# Zuino_XS_PsyFi32.net
KiCad netlist of a schematic drawn in EAGLE
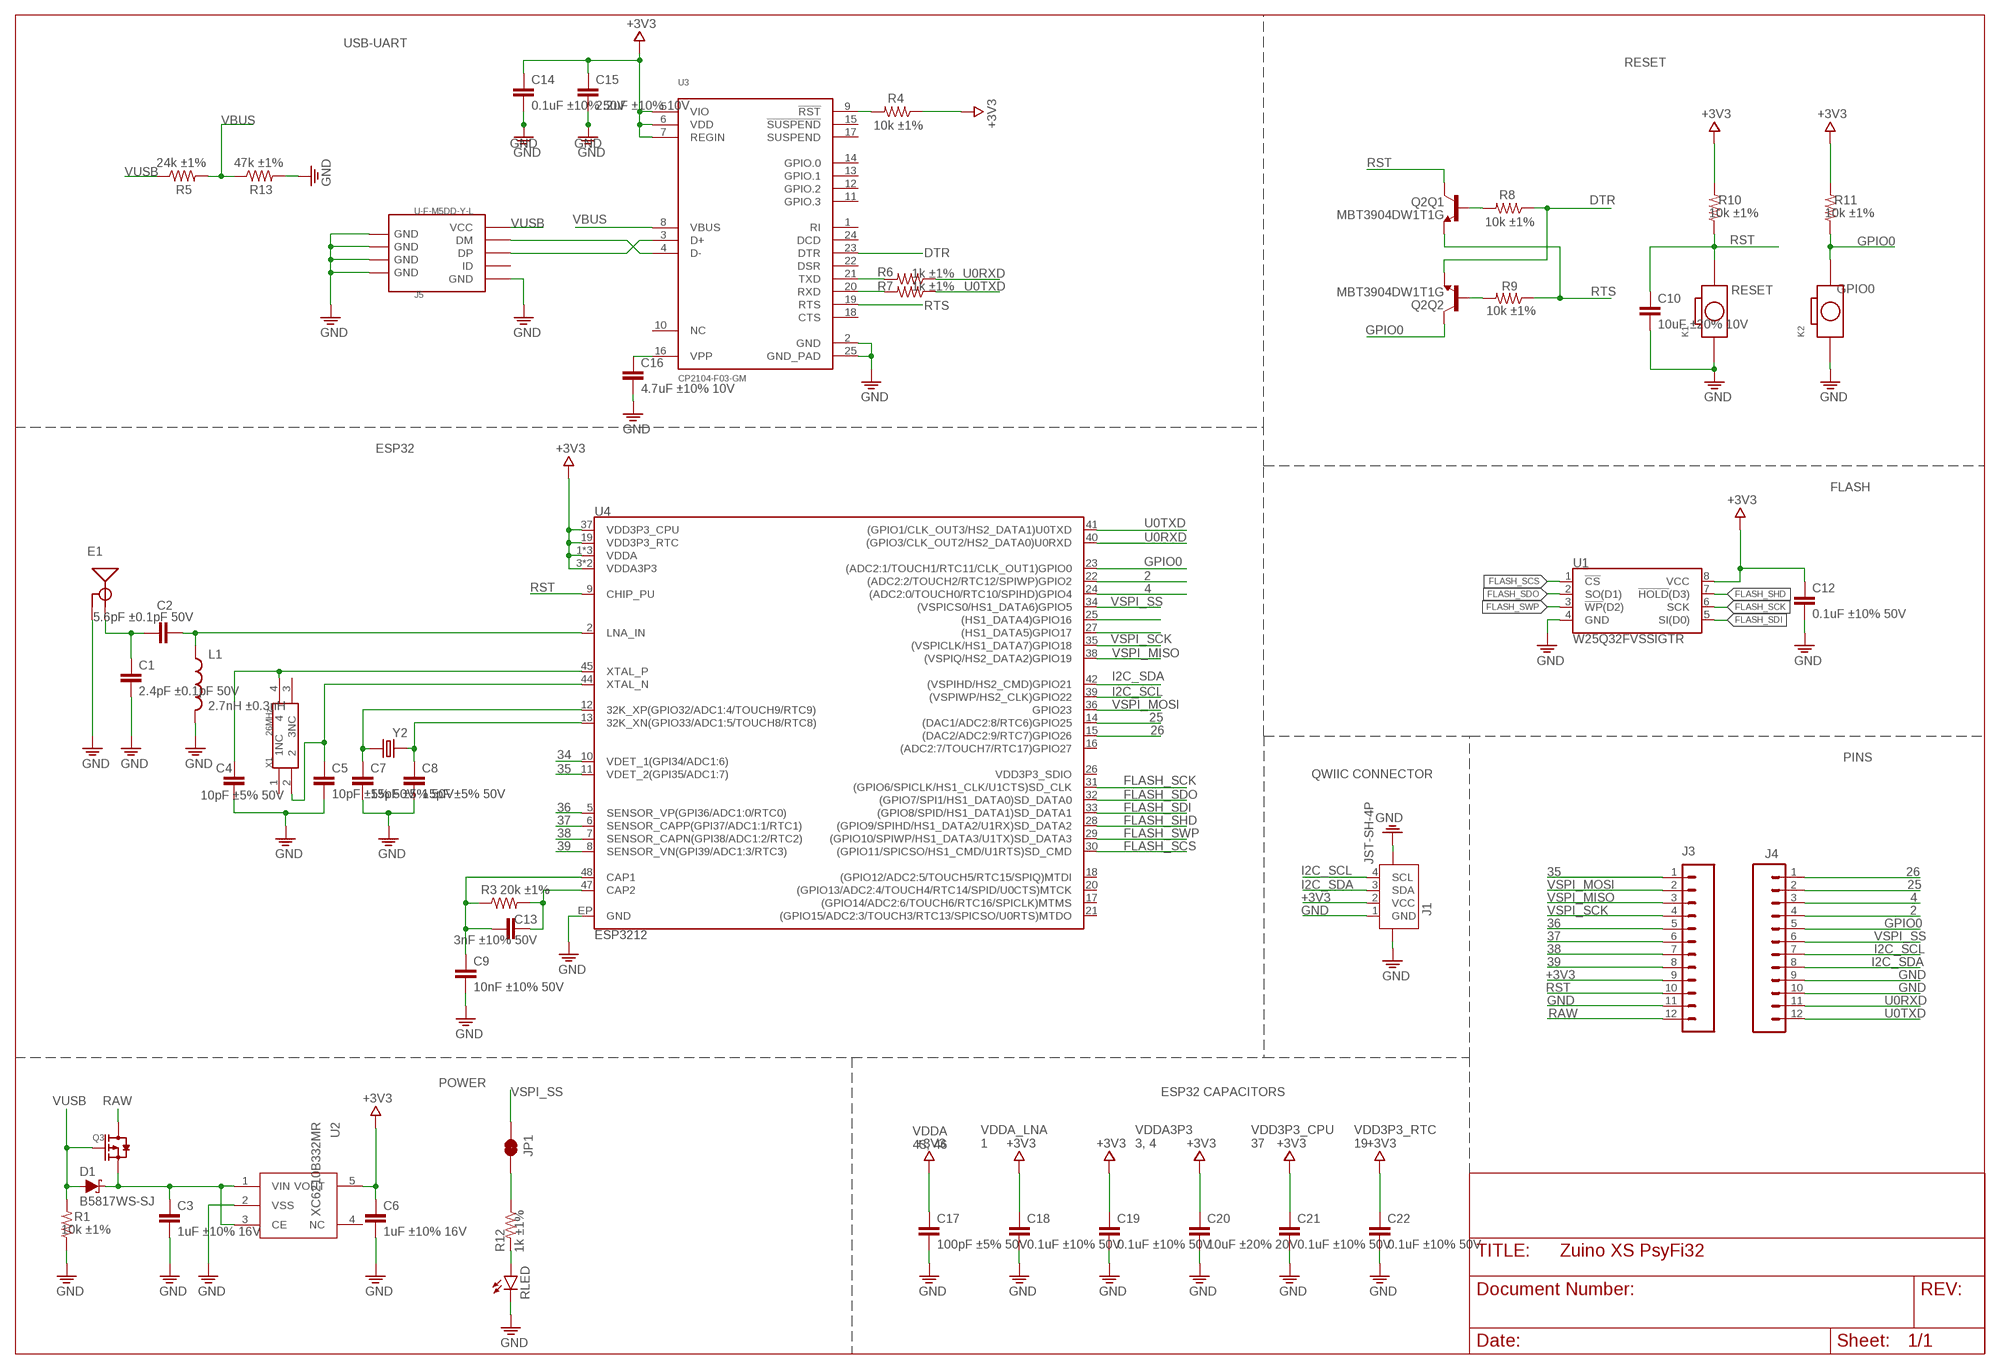
[diagram p0: schematic, sheet 1]

(export (version "E")
  (design (tool "Eeschema 10.0.6"))
  (components
    (comp (ref "C1")
      (value "2.4pF ±0.1pF 50V")
      (footprint "eagle-import:YAGEO_C_0402")
      (libsource (lib "eagle-import") (part "0.1UF"))
    )
    (comp (ref "C2")
      (value "5.6pF ±0.1pF 50V")
      (footprint "eagle-import:YAGEO_C_0402")
      (libsource (lib "eagle-import") (part "0.1UF"))
    )
    (comp (ref "C3")
      (value "1uF ±10% 16V")
      (footprint "eagle-import:YAGEO_C_0402")
      (libsource (lib "eagle-import") (part "0.1UF"))
    )
    (comp (ref "C4")
      (value "10pF ±5% 50V")
      (footprint "eagle-import:YAGEO_C_0402")
      (libsource (lib "eagle-import") (part "0.1UF"))
    )
    (comp (ref "C5")
      (value "10pF ±5% 50V")
      (footprint "eagle-import:YAGEO_C_0402")
      (libsource (lib "eagle-import") (part "0.1UF"))
    )
    (comp (ref "C6")
      (value "1uF ±10% 16V")
      (footprint "eagle-import:YAGEO_C_0402")
      (libsource (lib "eagle-import") (part "0.1UF"))
    )
    (comp (ref "C7")
      (value "15pF ±5% 50V")
      (footprint "eagle-import:YAGEO_C_0402")
      (libsource (lib "eagle-import") (part "0.1UF"))
    )
    (comp (ref "C8")
      (value "15pF ±5% 50V")
      (footprint "eagle-import:YAGEO_C_0402")
      (libsource (lib "eagle-import") (part "0.1UF"))
    )
    (comp (ref "C9")
      (value "10nF ±10% 50V")
      (footprint "eagle-import:YAGEO_C_0402")
      (libsource (lib "eagle-import") (part "0.1UF"))
    )
    (comp (ref "C10")
      (value "10uF ±20% 10V")
      (footprint "eagle-import:YAGEO_C_0402")
      (libsource (lib "eagle-import") (part "0.1UF"))
    )
    (comp (ref "C12")
      (value "0.1uF ±10% 50V")
      (footprint "eagle-import:YAGEO_C_0402")
      (libsource (lib "eagle-import") (part "0.1UF"))
    )
    (comp (ref "C13")
      (value "3nF ±10% 50V")
      (footprint "eagle-import:YAGEO_C_0402")
      (libsource (lib "eagle-import") (part "0.1UF"))
    )
    (comp (ref "C14")
      (value "0.1uF ±10% 50V")
      (footprint "eagle-import:YAGEO_C_0402")
      (libsource (lib "eagle-import") (part "0.1UF"))
    )
    (comp (ref "C15")
      (value "2.2uF ±10% 10V")
      (footprint "eagle-import:YAGEO_C_0402")
      (libsource (lib "eagle-import") (part "0.1UF"))
    )
    (comp (ref "C16")
      (value "4.7uF ±10% 10V")
      (footprint "eagle-import:YAGEO_C_0402")
      (libsource (lib "eagle-import") (part "0.1UF"))
    )
    (comp (ref "C17")
      (value "100pF ±5% 50V")
      (footprint "eagle-import:YAGEO_C_0402")
      (libsource (lib "eagle-import") (part "0.1UF"))
    )
    (comp (ref "C18")
      (value "0.1uF ±10% 50V")
      (footprint "eagle-import:YAGEO_C_0402")
      (libsource (lib "eagle-import") (part "0.1UF"))
    )
    (comp (ref "C19")
      (value "0.1uF ±10% 50V")
      (footprint "eagle-import:YAGEO_C_0402")
      (libsource (lib "eagle-import") (part "0.1UF"))
    )
    (comp (ref "C20")
      (value "10uF ±20% 20V")
      (footprint "eagle-import:YAGEO_C_0402")
      (libsource (lib "eagle-import") (part "0.1UF"))
    )
    (comp (ref "C21")
      (value "0.1uF ±10% 50V")
      (footprint "eagle-import:YAGEO_C_0402")
      (libsource (lib "eagle-import") (part "0.1UF"))
    )
    (comp (ref "C22")
      (value "0.1uF ±10% 50V")
      (footprint "eagle-import:YAGEO_C_0402")
      (libsource (lib "eagle-import") (part "0.1UF"))
    )
    (comp (ref "D1")
      (value "B5817WS-SJ")
      (footprint "eagle-import:SOD-323")
      (libsource (lib "eagle-import") (part "DIODE-SCHOTTKY-BAT20J"))
    )
    (comp (ref "D2")
      (value "RLED")
      (footprint "eagle-import:LED_HSMH-C190")
      (libsource (lib "eagle-import") (part "LED"))
    )
    (comp (ref "E1")
      (value "ANTENNA-GROUNDED")
      (footprint "eagle-import:ANTENNA_ESP32")
      (libsource (lib "eagle-import") (part "ANTENNA-GROUNDED"))
    )
    (comp (ref "J1")
      (value "JST-SH-4P")
      (footprint "eagle-import:JST-SH-4P-90")
      (libsource (lib "eagle-import") (part "JST-SH-4P"))
    )
    (comp (ref "J3")
      (value "CONN_12")
      (footprint "eagle-import:1X12")
      (libsource (lib "eagle-import") (part "CONN_12"))
    )
    (comp (ref "J4")
      (value "CONN_12")
      (footprint "eagle-import:1X12")
      (libsource (lib "eagle-import") (part "CONN_12"))
    )
    (comp (ref "J5")
      (value "U-F-M5DD-Y-L")
      (footprint "eagle-import:MICRO-SMD")
      (libsource (lib "eagle-import") (part "USB-MICROE"))
    )
    (comp (ref "JP1")
      (value "JUMPER-SMT_2_NC_TRACE_SILK")
      (footprint "eagle-import:SMT-JUMPER_2_NC_TRACE_SILK")
      (libsource (lib "eagle-import") (part "JUMPER-SMT_2_NC_TRACE_SILK"))
    )
    (comp (ref "K1")
      (value "BOTTON-2PSKRKAEE020")
      (footprint "eagle-import:SKRKAEE020")
      (libsource (lib "eagle-import") (part "BOTTON-2PSKRKAEE020"))
    )
    (comp (ref "K2")
      (value "BOTTON-2PSKRKAEE020")
      (footprint "eagle-import:SKRKAEE020")
      (libsource (lib "eagle-import") (part "BOTTON-2PSKRKAEE020"))
    )
    (comp (ref "L1")
      (value "2.7nH ±0.3nH")
      (footprint "eagle-import:INDUCTOR_HK10052N7S-T")
      (libsource (lib "eagle-import") (part "INDUCTOR"))
    )
    (comp (ref "Q2")
      (value "MBT3904DW1T1G")
      (footprint "eagle-import:SC70-6")
      (fields
        (field (name "DIGIKEY") "https://www.digikey.com/product-detail/en/on-semiconductor/MBT3904DW1T1G/MBT3904DW1T1GOSCT-ND/918012")
      )
      (libsource (lib "eagle-import") (part "MBT3904DW1T1"))
    )
    (comp (ref "Q3")
      (value "MOSFET-P-323")
      (footprint "eagle-import:SOT-323")
      (libsource (lib "eagle-import") (part "MOSFET-P-323"))
    )
    (comp (ref "R1")
      (value "10k ±1%")
      (footprint "eagle-import:YAGEO_R_0402")
      (libsource (lib "eagle-import") (part "RESISTOR"))
    )
    (comp (ref "R3")
      (value "20k ±1%")
      (footprint "eagle-import:YAGEO_R_0402")
      (libsource (lib "eagle-import") (part "RESISTOR"))
    )
    (comp (ref "R4")
      (value "10k ±1%")
      (footprint "eagle-import:YAGEO_R_0402")
      (libsource (lib "eagle-import") (part "RESISTOR"))
    )
    (comp (ref "R5")
      (value "24k ±1%")
      (footprint "eagle-import:YAGEO_R_0402")
      (libsource (lib "eagle-import") (part "RESISTOR"))
    )
    (comp (ref "R6")
      (value "1k ±1%")
      (footprint "eagle-import:YAGEO_R_0402")
      (libsource (lib "eagle-import") (part "RESISTOR"))
    )
    (comp (ref "R7")
      (value "1k ±1%")
      (footprint "eagle-import:YAGEO_R_0402")
      (libsource (lib "eagle-import") (part "RESISTOR"))
    )
    (comp (ref "R8")
      (value "10k ±1%")
      (footprint "eagle-import:YAGEO_R_0402")
      (libsource (lib "eagle-import") (part "RESISTOR"))
    )
    (comp (ref "R9")
      (value "10k ±1%")
      (footprint "eagle-import:YAGEO_R_0402")
      (libsource (lib "eagle-import") (part "RESISTOR"))
    )
    (comp (ref "R10")
      (value "10k ±1%")
      (footprint "eagle-import:YAGEO_R_0402")
      (libsource (lib "eagle-import") (part "RESISTOR"))
    )
    (comp (ref "R11")
      (value "10k ±1%")
      (footprint "eagle-import:YAGEO_R_0402")
      (libsource (lib "eagle-import") (part "RESISTOR"))
    )
    (comp (ref "R12")
      (value "1k ±1%")
      (footprint "eagle-import:YAGEO_R_0402")
      (libsource (lib "eagle-import") (part "RESISTOR"))
    )
    (comp (ref "R13")
      (value "47k ±1%")
      (footprint "eagle-import:YAGEO_R_0402")
      (libsource (lib "eagle-import") (part "RESISTOR"))
    )
    (comp (ref "U1")
      (value "W25Q32FVSSIGTR")
      (footprint "eagle-import:SOIC-8")
      (libsource (lib "eagle-import") (part "W25Q32FVSS"))
    )
    (comp (ref "U2")
      (value "XC6210B332MR")
      (footprint "eagle-import:SOT23-5")
      (libsource (lib "eagle-import") (part "XC6210"))
    )
    (comp (ref "U3")
      (value "CP2104-F03-GM")
      (footprint "eagle-import:QFN24-CP2104")
      (libsource (lib "eagle-import") (part "CP2104-F03-GM"))
    )
    (comp (ref "U4")
      (value "ESP3212")
      (footprint "eagle-import:QFN48-0.4MM")
      (libsource (lib "eagle-import") (part "ESP3212"))
    )
    (comp (ref "X1")
      (value "26MHz")
      (footprint "eagle-import:4P-SMD-2X1.6MM")
      (libsource (lib "eagle-import") (part "CRYSTAL-XTAL-4P"))
    )
    (comp (ref "Y2")
      (value "32.768kHz")
      (footprint "eagle-import:CRYSTAL_2012")
      (libsource (lib "eagle-import") (part "CRYSTAL-Y2012"))
    )
  )
  (nets
    (net (code "1") (name "+3V3") (class "Default")
      (node (ref "C12") (pin "1") (pinfunction "1_1") (pintype "passive"))
      (node (ref "C14") (pin "1") (pinfunction "1_1") (pintype "passive"))
      (node (ref "C15") (pin "1") (pinfunction "1_1") (pintype "passive"))
      (node (ref "C17") (pin "1") (pinfunction "1_1") (pintype "passive"))
      (node (ref "C18") (pin "1") (pinfunction "1_1") (pintype "passive"))
      (node (ref "C19") (pin "1") (pinfunction "1_1") (pintype "passive"))
      (node (ref "C20") (pin "1") (pinfunction "1_1") (pintype "passive"))
      (node (ref "C21") (pin "1") (pinfunction "1_1") (pintype "passive"))
      (node (ref "C22") (pin "1") (pinfunction "1_1") (pintype "passive"))
      (node (ref "C6") (pin "1") (pinfunction "1_1") (pintype "passive"))
      (node (ref "J1") (pin "2") (pinfunction "VCC_2") (pintype "bidirectional"))
      (node (ref "J3") (pin "9") (pinfunction "9_9") (pintype "passive"))
      (node (ref "R10") (pin "2") (pinfunction "2_2") (pintype "passive"))
      (node (ref "R11") (pin "2") (pinfunction "2_2") (pintype "passive"))
      (node (ref "R4") (pin "1") (pinfunction "1_1") (pintype "passive"))
      (node (ref "U1") (pin "8") (pinfunction "VCC_8") (pintype "bidirectional"))
      (node (ref "U2") (pin "5") (pinfunction "VOUT_5") (pintype "bidirectional"))
      (node (ref "U3") (pin "5") (pinfunction "VIO_5") (pintype "bidirectional"))
      (node (ref "U3") (pin "6") (pinfunction "VDD_6") (pintype "bidirectional"))
      (node (ref "U3") (pin "7") (pinfunction "REGIN_7") (pintype "bidirectional"))
      (node (ref "U4") (pin "1") (pinfunction "VDDA_1") (pintype "bidirectional"))
      (node (ref "U4") (pin "19") (pinfunction "VDD3P3_RTC_19") (pintype "bidirectional"))
      (node (ref "U4") (pin "3") (pinfunction "VDDA3P3_3") (pintype "bidirectional"))
      (node (ref "U4") (pin "37") (pinfunction "VDD3P3_CPU_37") (pintype "bidirectional"))
      (node (ref "U4") (pin "4") (pinfunction "VDDA3P3_4") (pintype "bidirectional"))
      (node (ref "U4") (pin "43") (pinfunction "VDDA_43") (pintype "bidirectional"))
      (node (ref "U4") (pin "46") (pinfunction "VDDA_46") (pintype "bidirectional"))
    )
    (net (code "2") (name "/2") (class "Default")
      (node (ref "J4") (pin "4") (pinfunction "4_4") (pintype "passive"))
      (node (ref "U4") (pin "22") (pinfunction "(ADC2:2/TOUCH2/RTC12/SPIWP)GPIO2_22") (pintype "bidirectional"))
    )
    (net (code "3") (name "/4") (class "Default")
      (node (ref "J4") (pin "3") (pinfunction "3_3") (pintype "passive"))
      (node (ref "U4") (pin "24") (pinfunction "(ADC2:0/TOUCH0/RTC10/SPIHD)GPIO4_24") (pintype "bidirectional"))
    )
    (net (code "4") (name "/25") (class "Default")
      (node (ref "J4") (pin "2") (pinfunction "2_2") (pintype "passive"))
      (node (ref "U4") (pin "14") (pinfunction "(DAC1/ADC2:8/RTC6)GPIO25_14") (pintype "bidirectional"))
    )
    (net (code "5") (name "/26") (class "Default")
      (node (ref "J4") (pin "1") (pinfunction "1_1") (pintype "passive"))
      (node (ref "U4") (pin "15") (pinfunction "(DAC2/ADC2:9/RTC7)GPIO26_15") (pintype "bidirectional"))
    )
    (net (code "6") (name "/34") (class "Default")
      (node (ref "U4") (pin "10") (pinfunction "VDET_1(GPI34/ADC1:6)_10") (pintype "bidirectional"))
    )
    (net (code "7") (name "/35") (class "Default")
      (node (ref "J3") (pin "1") (pinfunction "1_1") (pintype "passive"))
      (node (ref "U4") (pin "11") (pinfunction "VDET_2(GPI35/ADC1:7)_11") (pintype "bidirectional"))
    )
    (net (code "8") (name "/36") (class "Default")
      (node (ref "J3") (pin "5") (pinfunction "5_5") (pintype "passive"))
      (node (ref "U4") (pin "5") (pinfunction "SENSOR_VP(GPI36/ADC1:0/RTC0)_5") (pintype "bidirectional"))
    )
    (net (code "9") (name "/37") (class "Default")
      (node (ref "J3") (pin "6") (pinfunction "6_6") (pintype "passive"))
      (node (ref "U4") (pin "6") (pinfunction "SENSOR_CAPP(GPI37/ADC1:1/RTC1)_6") (pintype "bidirectional"))
    )
    (net (code "10") (name "/38") (class "Default")
      (node (ref "J3") (pin "7") (pinfunction "7_7") (pintype "passive"))
      (node (ref "U4") (pin "7") (pinfunction "SENSOR_CAPN(GPI38/ADC1:2/RTC2)_7") (pintype "bidirectional"))
    )
    (net (code "11") (name "/39") (class "Default")
      (node (ref "J3") (pin "8") (pinfunction "8_8") (pintype "passive"))
      (node (ref "U4") (pin "8") (pinfunction "SENSOR_VN(GPI39/ADC1:3/RTC3)_8") (pintype "bidirectional"))
    )
    (net (code "12") (name "/DTR") (class "Default")
      (node (ref "Q2") (pin "1") (pinfunction "E_1") (pintype "passive"))
      (node (ref "R8") (pin "1") (pinfunction "1_1") (pintype "passive"))
      (node (ref "U3") (pin "23") (pinfunction "DTR_23") (pintype "bidirectional"))
    )
    (net (code "13") (name "/GPIO0") (class "Default")
      (node (ref "J4") (pin "5") (pinfunction "5_5") (pintype "passive"))
      (node (ref "K2") (pin "2") (pinfunction "2_2") (pintype "bidirectional"))
      (node (ref "Q2") (pin "6") (pinfunction "C_6") (pintype "passive"))
      (node (ref "R11") (pin "1") (pinfunction "1_1") (pintype "passive"))
      (node (ref "U4") (pin "23") (pinfunction "(ADC2:1/TOUCH1/RTC11/CLK_OUT1)GPIO0_23") (pintype "bidirectional"))
    )
    (net (code "14") (name "/I2C_SCL") (class "Default")
      (node (ref "J1") (pin "4") (pinfunction "SCL_4") (pintype "bidirectional"))
      (node (ref "J4") (pin "7") (pinfunction "7_7") (pintype "passive"))
      (node (ref "U4") (pin "39") (pinfunction "(VSPIWP/HS2_CLK)GPIO22_39") (pintype "bidirectional"))
    )
    (net (code "15") (name "/I2C_SDA") (class "Default")
      (node (ref "J1") (pin "3") (pinfunction "SDA_3") (pintype "bidirectional"))
      (node (ref "J4") (pin "8") (pinfunction "8_8") (pintype "passive"))
      (node (ref "U4") (pin "42") (pinfunction "(VSPIHD/HS2_CMD)GPIO21_42") (pintype "bidirectional"))
    )
    (net (code "16") (name "/RAW") (class "Default")
      (node (ref "J3") (pin "12") (pinfunction "12_12") (pintype "passive"))
      (node (ref "Q3") (pin "3") (pinfunction "D_3") (pintype "passive"))
    )
    (net (code "17") (name "/RST") (class "Default")
      (node (ref "C10") (pin "1") (pinfunction "1_1") (pintype "passive"))
      (node (ref "J3") (pin "10") (pinfunction "10_10") (pintype "passive"))
      (node (ref "K1") (pin "2") (pinfunction "2_2") (pintype "bidirectional"))
      (node (ref "Q2") (pin "3") (pinfunction "C_3") (pintype "passive"))
      (node (ref "R10") (pin "1") (pinfunction "1_1") (pintype "passive"))
      (node (ref "U4") (pin "9") (pinfunction "CHIP_PU_9") (pintype "bidirectional"))
    )
    (net (code "18") (name "/RTS") (class "Default")
      (node (ref "Q2") (pin "4") (pinfunction "E_4") (pintype "passive"))
      (node (ref "R9") (pin "1") (pinfunction "1_1") (pintype "passive"))
      (node (ref "U3") (pin "19") (pinfunction "RTS_19") (pintype "bidirectional"))
    )
    (net (code "19") (name "/U0RXD") (class "Default")
      (node (ref "J4") (pin "11") (pinfunction "11_11") (pintype "passive"))
      (node (ref "R6") (pin "1") (pinfunction "1_1") (pintype "passive"))
      (node (ref "U4") (pin "40") (pinfunction "(GPIO3/CLK_OUT2/HS2_DATA0)U0RXD_40") (pintype "bidirectional"))
    )
    (net (code "20") (name "/U0TXD") (class "Default")
      (node (ref "J4") (pin "12") (pinfunction "12_12") (pintype "passive"))
      (node (ref "R7") (pin "1") (pinfunction "1_1") (pintype "passive"))
      (node (ref "U4") (pin "41") (pinfunction "(GPIO1/CLK_OUT3/HS2_DATA1)U0TXD_41") (pintype "bidirectional"))
    )
    (net (code "21") (name "/VBUS") (class "Default")
      (node (ref "R13") (pin "1") (pinfunction "1_1") (pintype "passive"))
      (node (ref "R5") (pin "2") (pinfunction "2_2") (pintype "passive"))
      (node (ref "U3") (pin "8") (pinfunction "VBUS_8") (pintype "bidirectional"))
    )
    (net (code "22") (name "/VSPI_MISO") (class "Default")
      (node (ref "J3") (pin "3") (pinfunction "3_3") (pintype "passive"))
      (node (ref "U4") (pin "38") (pinfunction "(VSPIQ/HS2_DATA2)GPIO19_38") (pintype "bidirectional"))
    )
    (net (code "23") (name "/VSPI_MOSI") (class "Default")
      (node (ref "J3") (pin "2") (pinfunction "2_2") (pintype "passive"))
      (node (ref "U4") (pin "36") (pinfunction "GPIO23_36") (pintype "bidirectional"))
    )
    (net (code "24") (name "/VSPI_SCK") (class "Default")
      (node (ref "J3") (pin "4") (pinfunction "4_4") (pintype "passive"))
      (node (ref "U4") (pin "35") (pinfunction "(VSPICLK/HS1_DATA7)GPIO18_35") (pintype "bidirectional"))
    )
    (net (code "25") (name "/VSPI_SS") (class "Default")
      (node (ref "J4") (pin "6") (pinfunction "6_6") (pintype "passive"))
      (node (ref "JP1") (pin "1") (pinfunction "1_1") (pintype "passive"))
      (node (ref "U4") (pin "34") (pinfunction "(VSPICS0/HS1_DATA6)GPIO5_34") (pintype "bidirectional"))
    )
    (net (code "26") (name "/VUSB") (class "Default")
      (node (ref "D1") (pin "A") (pinfunction "A_A") (pintype "passive"))
      (node (ref "J5") (pin "VBUS") (pinfunction "VCC_VBUS") (pintype "bidirectional"))
      (node (ref "Q3") (pin "1") (pinfunction "G_1") (pintype "passive"))
      (node (ref "R1") (pin "2") (pinfunction "2_2") (pintype "passive"))
      (node (ref "R5") (pin "1") (pinfunction "1_1") (pintype "passive"))
    )
    (net (code "27") (name "FLASH_SCK") (class "Default")
      (node (ref "U1") (pin "6") (pinfunction "SCK_6") (pintype "bidirectional"))
      (node (ref "U4") (pin "31") (pinfunction "(GPIO6/SPICLK/HS1_CLK/U1CTS)SD_CLK_31") (pintype "bidirectional"))
    )
    (net (code "28") (name "FLASH_SCS") (class "Default")
      (node (ref "U1") (pin "1") (pinfunction "~{CS}_1") (pintype "bidirectional"))
      (node (ref "U4") (pin "30") (pinfunction "(GPIO11/SPICSO/HS1_CMD/U1RTS)SD_CMD_30") (pintype "bidirectional"))
    )
    (net (code "29") (name "FLASH_SDI") (class "Default")
      (node (ref "U1") (pin "5") (pinfunction "SI(D0)_5") (pintype "bidirectional"))
      (node (ref "U4") (pin "33") (pinfunction "(GPIO8/SPID/HS1_DATA1)SD_DATA1_33") (pintype "bidirectional"))
    )
    (net (code "30") (name "FLASH_SDO") (class "Default")
      (node (ref "U1") (pin "2") (pinfunction "SO(D1)_2") (pintype "bidirectional"))
      (node (ref "U4") (pin "32") (pinfunction "(GPIO7/SPI1/HS1_DATA0)SD_DATA0_32") (pintype "bidirectional"))
    )
    (net (code "31") (name "FLASH_SHD") (class "Default")
      (node (ref "U1") (pin "7") (pinfunction "~{HOLD}(D3)_7") (pintype "bidirectional"))
      (node (ref "U4") (pin "28") (pinfunction "(GPIO9/SPIHD/HS1_DATA2/U1RX)SD_DATA2_28") (pintype "bidirectional"))
    )
    (net (code "32") (name "FLASH_SWP") (class "Default")
      (node (ref "U1") (pin "3") (pinfunction "~{WP}(D2)_3") (pintype "bidirectional"))
      (node (ref "U4") (pin "29") (pinfunction "(GPIO10/SPIWP/HS1_DATA3/U1TX)SD_DATA3_29") (pintype "bidirectional"))
    )
    (net (code "33") (name "GND") (class "Default")
      (node (ref "C1") (pin "2") (pinfunction "2_2") (pintype "passive"))
      (node (ref "C10") (pin "2") (pinfunction "2_2") (pintype "passive"))
      (node (ref "C12") (pin "2") (pinfunction "2_2") (pintype "passive"))
      (node (ref "C14") (pin "2") (pinfunction "2_2") (pintype "passive"))
      (node (ref "C15") (pin "2") (pinfunction "2_2") (pintype "passive"))
      (node (ref "C16") (pin "2") (pinfunction "2_2") (pintype "passive"))
      (node (ref "C17") (pin "2") (pinfunction "2_2") (pintype "passive"))
      (node (ref "C18") (pin "2") (pinfunction "2_2") (pintype "passive"))
      (node (ref "C19") (pin "2") (pinfunction "2_2") (pintype "passive"))
      (node (ref "C20") (pin "2") (pinfunction "2_2") (pintype "passive"))
      (node (ref "C21") (pin "2") (pinfunction "2_2") (pintype "passive"))
      (node (ref "C22") (pin "2") (pinfunction "2_2") (pintype "passive"))
      (node (ref "C3") (pin "2") (pinfunction "2_2") (pintype "passive"))
      (node (ref "C4") (pin "2") (pinfunction "2_2") (pintype "passive"))
      (node (ref "C5") (pin "2") (pinfunction "2_2") (pintype "passive"))
      (node (ref "C6") (pin "2") (pinfunction "2_2") (pintype "passive"))
      (node (ref "C7") (pin "2") (pinfunction "2_2") (pintype "passive"))
      (node (ref "C8") (pin "2") (pinfunction "2_2") (pintype "passive"))
      (node (ref "C9") (pin "2") (pinfunction "2_2") (pintype "passive"))
      (node (ref "D2") (pin "1") (pinfunction "C_1") (pintype "passive"))
      (node (ref "E1") (pin "GND") (pinfunction "GND_GND") (pintype "bidirectional"))
      (node (ref "J1") (pin "1") (pinfunction "GND_1") (pintype "bidirectional"))
      (node (ref "J1") (pin "5") (pinfunction "5_5") (pintype "bidirectional"))
      (node (ref "J1") (pin "6") (pinfunction "6_6") (pintype "bidirectional"))
      (node (ref "J3") (pin "11") (pinfunction "11_11") (pintype "passive"))
      (node (ref "J4") (pin "10") (pinfunction "10_10") (pintype "passive"))
      (node (ref "J4") (pin "9") (pinfunction "9_9") (pintype "passive"))
      (node (ref "J5") (pin "GND") (pinfunction "GND_GND") (pintype "bidirectional"))
      (node (ref "J5") (pin "S1") (pinfunction "GND_S1") (pintype "bidirectional"))
      (node (ref "J5") (pin "S1@1") (pinfunction "GND_S1@1") (pintype "bidirectional"))
      (node (ref "J5") (pin "S1@2") (pinfunction "GND_S1@2") (pintype "bidirectional"))
      (node (ref "J5") (pin "S2") (pinfunction "GND_S2") (pintype "bidirectional"))
      (node (ref "J5") (pin "S2@1") (pinfunction "GND_S2@1") (pintype "bidirectional"))
      (node (ref "J5") (pin "S2@2") (pinfunction "GND_S2@2") (pintype "bidirectional"))
      (node (ref "J5") (pin "S3") (pinfunction "GND_S3") (pintype "bidirectional"))
      (node (ref "J5") (pin "S3@1") (pinfunction "GND_S3@1") (pintype "bidirectional"))
      (node (ref "J5") (pin "S3@2") (pinfunction "GND_S3@2") (pintype "bidirectional"))
      (node (ref "J5") (pin "S4") (pinfunction "GND_S4") (pintype "bidirectional"))
      (node (ref "J5") (pin "S4@1") (pinfunction "GND_S4@1") (pintype "bidirectional"))
      (node (ref "J5") (pin "S4@2") (pinfunction "GND_S4@2") (pintype "bidirectional"))
      (node (ref "K1") (pin "1") (pinfunction "1_1") (pintype "bidirectional"))
      (node (ref "K2") (pin "1") (pinfunction "1_1") (pintype "bidirectional"))
      (node (ref "L1") (pin "2") (pinfunction "2_2") (pintype "passive"))
      (node (ref "R1") (pin "1") (pinfunction "1_1") (pintype "passive"))
      (node (ref "R13") (pin "2") (pinfunction "2_2") (pintype "passive"))
      (node (ref "U1") (pin "4") (pinfunction "GND_4") (pintype "bidirectional"))
      (node (ref "U2") (pin "2") (pinfunction "VSS_2") (pintype "bidirectional"))
      (node (ref "U3") (pin "2") (pinfunction "GND_2") (pintype "bidirectional"))
      (node (ref "U3") (pin "25") (pinfunction "GND_PAD_25") (pintype "bidirectional"))
      (node (ref "U4") (pin "EP") (pinfunction "GND_EP") (pintype "bidirectional"))
    )
    (net (code "34") (name "Net-(D2-A)") (class "Default")
      (node (ref "D2") (pin "2") (pinfunction "A_2") (pintype "passive"))
      (node (ref "R12") (pin "2") (pinfunction "2_2") (pintype "passive"))
    )
    (net (code "35") (name "Net-(E1-SIGNAL)") (class "Default")
      (node (ref "C1") (pin "1") (pinfunction "1_1") (pintype "passive"))
      (node (ref "C2") (pin "1") (pinfunction "1_1") (pintype "passive"))
      (node (ref "E1") (pin "ANT") (pinfunction "SIGNAL_ANT") (pintype "bidirectional"))
    )
    (net (code "36") (name "Net-(J5-DM)") (class "Default")
      (node (ref "J5") (pin "D-") (pinfunction "DM_D-") (pintype "bidirectional"))
      (node (ref "U3") (pin "4") (pinfunction "D-_4") (pintype "bidirectional"))
    )
    (net (code "37") (name "Net-(J5-DP)") (class "Default")
      (node (ref "J5") (pin "D+") (pinfunction "DP_D+") (pintype "bidirectional"))
      (node (ref "U3") (pin "3") (pinfunction "D+_3") (pintype "bidirectional"))
    )
    (net (code "38") (name "Net-(JP1-Pad2)") (class "Default")
      (node (ref "JP1") (pin "2") (pinfunction "2_2") (pintype "passive"))
      (node (ref "R12") (pin "1") (pinfunction "1_1") (pintype "passive"))
    )
    (net (code "39") (name "Net-(Q2A-B)") (class "Default")
      (node (ref "Q2") (pin "5") (pinfunction "B_5") (pintype "passive"))
      (node (ref "R8") (pin "2") (pinfunction "2_2") (pintype "passive"))
    )
    (net (code "40") (name "Net-(Q2B-B)") (class "Default")
      (node (ref "Q2") (pin "2") (pinfunction "B_2") (pintype "passive"))
      (node (ref "R9") (pin "2") (pinfunction "2_2") (pintype "passive"))
    )
    (net (code "41") (name "Net-(Q3-S)") (class "Default")
      (node (ref "C3") (pin "1") (pinfunction "1_1") (pintype "passive"))
      (node (ref "D1") (pin "C") (pinfunction "C_C") (pintype "passive"))
      (node (ref "Q3") (pin "2") (pinfunction "S_2") (pintype "passive"))
      (node (ref "U2") (pin "1") (pinfunction "VIN_1") (pintype "bidirectional"))
      (node (ref "U2") (pin "3") (pinfunction "CE_3") (pintype "bidirectional"))
    )
    (net (code "42") (name "Net-(U3-RXD)") (class "Default")
      (node (ref "R7") (pin "2") (pinfunction "2_2") (pintype "passive"))
      (node (ref "U3") (pin "20") (pinfunction "RXD_20") (pintype "bidirectional"))
    )
    (net (code "43") (name "Net-(U3-TXD)") (class "Default")
      (node (ref "R6") (pin "2") (pinfunction "2_2") (pintype "passive"))
      (node (ref "U3") (pin "21") (pinfunction "TXD_21") (pintype "bidirectional"))
    )
    (net (code "44") (name "Net-(U3-VPP)") (class "Default")
      (node (ref "C16") (pin "1") (pinfunction "1_1") (pintype "passive"))
      (node (ref "U3") (pin "16") (pinfunction "VPP_16") (pintype "bidirectional"))
    )
    (net (code "45") (name "Net-(U3-~{RST})") (class "Default")
      (node (ref "R4") (pin "2") (pinfunction "2_2") (pintype "passive"))
      (node (ref "U3") (pin "9") (pinfunction "~{RST}_9") (pintype "bidirectional"))
    )
    (net (code "46") (name "Net-(U4-32K_XN(GPIO33{slash}ADC1:5{slash}TOUCH8{slash}RTC8))") (class "Default")
      (node (ref "C8") (pin "1") (pinfunction "1_1") (pintype "passive"))
      (node (ref "U4") (pin "13") (pinfunction "32K_XN(GPIO33/ADC1:5/TOUCH8/RTC8)_13") (pintype "bidirectional"))
      (node (ref "Y2") (pin "2") (pinfunction "2_2") (pintype "passive"))
    )
    (net (code "47") (name "Net-(U4-32K_XP(GPIO32{slash}ADC1:4{slash}TOUCH9{slash}RTC9))") (class "Default")
      (node (ref "C7") (pin "1") (pinfunction "1_1") (pintype "passive"))
      (node (ref "U4") (pin "12") (pinfunction "32K_XP(GPIO32/ADC1:4/TOUCH9/RTC9)_12") (pintype "bidirectional"))
      (node (ref "Y2") (pin "1") (pinfunction "1_1") (pintype "passive"))
    )
    (net (code "48") (name "Net-(U4-CAP1)") (class "Default")
      (node (ref "C13") (pin "1") (pinfunction "1_1") (pintype "passive"))
      (node (ref "C9") (pin "1") (pinfunction "1_1") (pintype "passive"))
      (node (ref "R3") (pin "1") (pinfunction "1_1") (pintype "passive"))
      (node (ref "U4") (pin "48") (pinfunction "CAP1_48") (pintype "bidirectional"))
    )
    (net (code "49") (name "Net-(U4-CAP2)") (class "Default")
      (node (ref "C13") (pin "2") (pinfunction "2_2") (pintype "passive"))
      (node (ref "R3") (pin "2") (pinfunction "2_2") (pintype "passive"))
      (node (ref "U4") (pin "47") (pinfunction "CAP2_47") (pintype "bidirectional"))
    )
    (net (code "50") (name "Net-(U4-LNA_IN)") (class "Default")
      (node (ref "C2") (pin "2") (pinfunction "2_2") (pintype "passive"))
      (node (ref "L1") (pin "1") (pinfunction "1_1") (pintype "passive"))
      (node (ref "U4") (pin "2") (pinfunction "LNA_IN_2") (pintype "bidirectional"))
    )
    (net (code "51") (name "Net-(U4-XTAL_N)") (class "Default")
      (node (ref "C5") (pin "1") (pinfunction "1_1") (pintype "passive"))
      (node (ref "U4") (pin "44") (pinfunction "XTAL_N_44") (pintype "bidirectional"))
      (node (ref "X1") (pin "2") (pinfunction "2_2") (pintype "bidirectional"))
    )
    (net (code "52") (name "Net-(U4-XTAL_P)") (class "Default")
      (node (ref "C4") (pin "1") (pinfunction "1_1") (pintype "passive"))
      (node (ref "U4") (pin "45") (pinfunction "XTAL_P_45") (pintype "bidirectional"))
      (node (ref "X1") (pin "4") (pinfunction "4_4") (pintype "bidirectional"))
    )
    (net (code "53") (name "unconnected-(J5-PadID)") (class "Default")
      (node (ref "J5") (pin "ID") (pinfunction "ID_ID") (pintype "bidirectional"))
    )
    (net (code "54") (name "unconnected-(U2-NC-Pad4)") (class "Default")
      (node (ref "U2") (pin "4") (pinfunction "NC_4") (pintype "bidirectional"))
    )
    (net (code "55") (name "unconnected-(U3-CTS-Pad18)") (class "Default")
      (node (ref "U3") (pin "18") (pinfunction "CTS_18") (pintype "bidirectional"))
    )
    (net (code "56") (name "unconnected-(U3-DCD-Pad24)") (class "Default")
      (node (ref "U3") (pin "24") (pinfunction "DCD_24") (pintype "bidirectional"))
    )
    (net (code "57") (name "unconnected-(U3-DSR-Pad22)") (class "Default")
      (node (ref "U3") (pin "22") (pinfunction "DSR_22") (pintype "bidirectional"))
    )
    (net (code "58") (name "unconnected-(U3-GPIO.0-Pad14)") (class "Default")
      (node (ref "U3") (pin "14") (pinfunction "GPIO.0_14") (pintype "bidirectional"))
    )
    (net (code "59") (name "unconnected-(U3-GPIO.1-Pad13)") (class "Default")
      (node (ref "U3") (pin "13") (pinfunction "GPIO.1_13") (pintype "bidirectional"))
    )
    (net (code "60") (name "unconnected-(U3-GPIO.2-Pad12)") (class "Default")
      (node (ref "U3") (pin "12") (pinfunction "GPIO.2_12") (pintype "bidirectional"))
    )
    (net (code "61") (name "unconnected-(U3-GPIO.3-Pad11)") (class "Default")
      (node (ref "U3") (pin "11") (pinfunction "GPIO.3_11") (pintype "bidirectional"))
    )
    (net (code "62") (name "unconnected-(U3-NC-Pad10)") (class "Default")
      (node (ref "U3") (pin "10") (pinfunction "NC_10") (pintype "bidirectional"))
    )
    (net (code "63") (name "unconnected-(U3-RI-Pad1)") (class "Default")
      (node (ref "U3") (pin "1") (pinfunction "RI_1") (pintype "bidirectional"))
    )
    (net (code "64") (name "unconnected-(U3-SUSPEND-Pad17)") (class "Default")
      (node (ref "U3") (pin "17") (pinfunction "SUSPEND_17") (pintype "bidirectional"))
    )
    (net (code "65") (name "unconnected-(U3-~{SUSPEND}-Pad15)") (class "Default")
      (node (ref "U3") (pin "15") (pinfunction "~{SUSPEND}_15") (pintype "bidirectional"))
    )
    (net (code "66") (name "unconnected-(U4-(ADC2:7{slash}TOUCH7{slash}RTC17)GPIO27-Pad16)") (class "Default")
      (node (ref "U4") (pin "16") (pinfunction "(ADC2:7/TOUCH7/RTC17)GPIO27_16") (pintype "bidirectional"))
    )
    (net (code "67") (name "unconnected-(U4-(GPIO12{slash}ADC2:5{slash}TOUCH5{slash}RTC15{slash}SPIQ)MTDI-Pad18)") (class "Default")
      (node (ref "U4") (pin "18") (pinfunction "(GPIO12/ADC2:5/TOUCH5/RTC15/SPIQ)MTDI_18") (pintype "bidirectional"))
    )
    (net (code "68") (name "unconnected-(U4-(GPIO13{slash}ADC2:4{slash}TOUCH4{slash}RTC14{slash}SPID{slash}U0CTS)MTCK-Pad20)") (class "Default")
      (node (ref "U4") (pin "20") (pinfunction "(GPIO13/ADC2:4/TOUCH4/RTC14/SPID/U0CTS)MTCK_20") (pintype "bidirectional"))
    )
    (net (code "69") (name "unconnected-(U4-(GPIO14{slash}ADC2:6{slash}TOUCH6{slash}RTC16{slash}SPICLK)MTMS-Pad17)") (class "Default")
      (node (ref "U4") (pin "17") (pinfunction "(GPIO14/ADC2:6/TOUCH6/RTC16/SPICLK)MTMS_17") (pintype "bidirectional"))
    )
    (net (code "70") (name "unconnected-(U4-(GPIO15{slash}ADC2:3{slash}TOUCH3{slash}RTC13{slash}SPICSO{slash}U0RTS)MTDO-Pad21)") (class "Default")
      (node (ref "U4") (pin "21") (pinfunction "(GPIO15/ADC2:3/TOUCH3/RTC13/SPICSO/U0RTS)MTDO_21") (pintype "bidirectional"))
    )
    (net (code "71") (name "unconnected-(U4-(HS1_DATA4)GPIO16-Pad25)") (class "Default")
      (node (ref "U4") (pin "25") (pinfunction "(HS1_DATA4)GPIO16_25") (pintype "bidirectional"))
    )
    (net (code "72") (name "unconnected-(U4-(HS1_DATA5)GPIO17-Pad27)") (class "Default")
      (node (ref "U4") (pin "27") (pinfunction "(HS1_DATA5)GPIO17_27") (pintype "bidirectional"))
    )
    (net (code "73") (name "unconnected-(U4-VDD3P3_SDIO-Pad26)") (class "Default")
      (node (ref "U4") (pin "26") (pinfunction "VDD3P3_SDIO_26") (pintype "bidirectional"))
    )
    (net (code "74") (name "unconnected-(X1-1NC-Pad1)") (class "Default")
      (node (ref "X1") (pin "1") (pinfunction "1NC_1") (pintype "bidirectional"))
    )
    (net (code "75") (name "unconnected-(X1-3NC-Pad3)") (class "Default")
      (node (ref "X1") (pin "3") (pinfunction "3NC_3") (pintype "bidirectional"))
    )
  )
)
